# eeZeePower.net
KiCad netlist of a schematic drawn in EAGLE
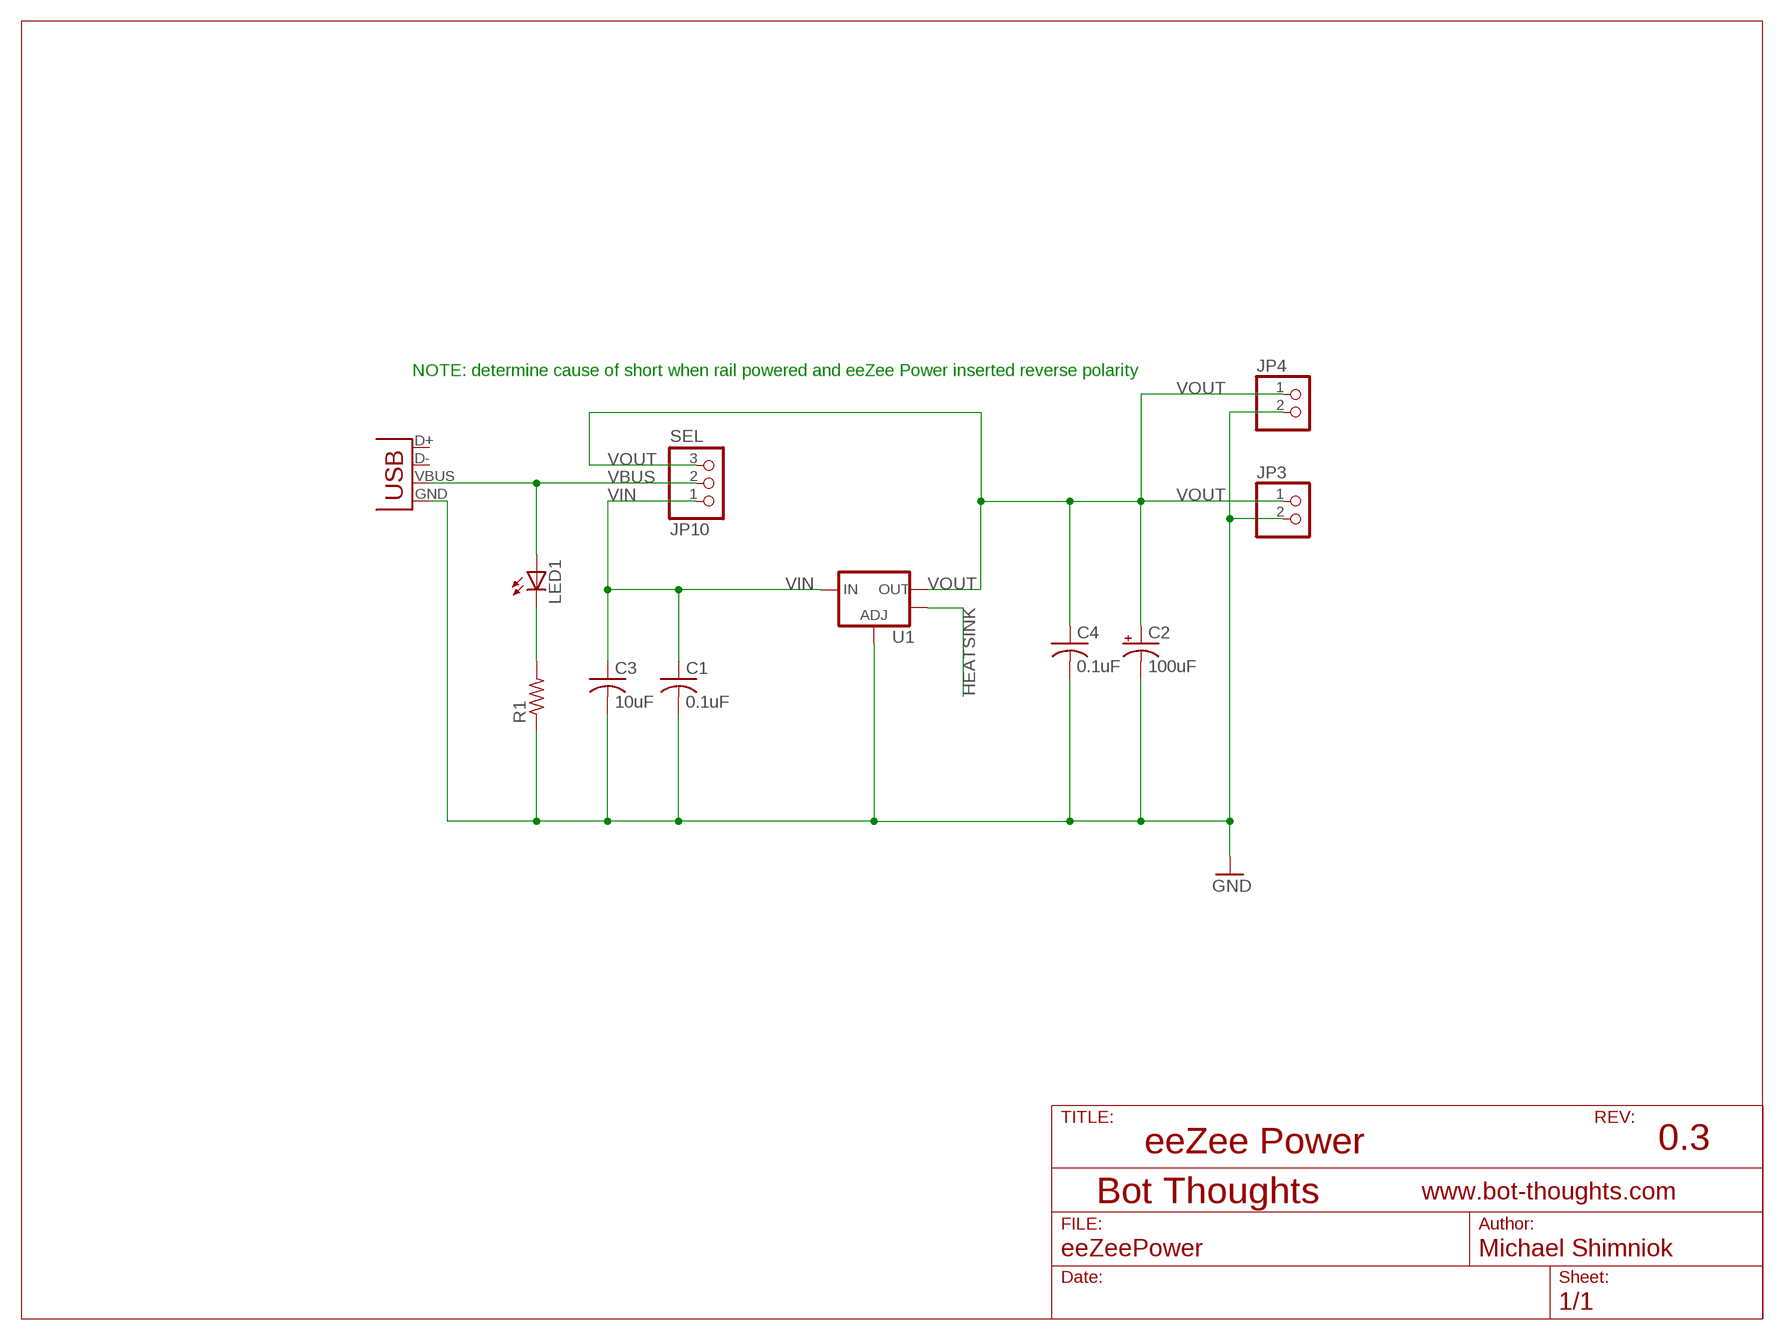
[diagram p0: schematic, sheet 1]

(export (version "E")
  (design (tool "Eeschema 10.0.6"))
  (components
    (comp (ref "C1")
      (value "0.1uF")
      (footprint "eagle-import:C0603")
      (libsource (lib "eagle-import") (part "C-USC0603"))
    )
    (comp (ref "C2")
      (value "100uF")
      (footprint "eagle-import:SMC_B")
      (libsource (lib "eagle-import") (part "CPOL-USSMCB"))
    )
    (comp (ref "C3")
      (value "10uF")
      (footprint "eagle-import:C0603")
      (libsource (lib "eagle-import") (part "C-USC0603"))
    )
    (comp (ref "C4")
      (value "0.1uF")
      (footprint "eagle-import:C0603")
      (libsource (lib "eagle-import") (part "C-USC0603"))
    )
    (comp (ref "JP1")
      (value "USBSMD")
      (footprint "eagle-import:USB-MINIB")
      (libsource (lib "eagle-import") (part "USBSMD"))
    )
    (comp (ref "JP3")
      (value "PINHD-1X02_2.54-S")
      (footprint "eagle-import:1X02-S")
      (libsource (lib "eagle-import") (part "PINHD-1X02_2.54-S"))
    )
    (comp (ref "JP4")
      (value "PINHD-1X02_2.54-S")
      (footprint "eagle-import:1X02-S")
      (libsource (lib "eagle-import") (part "PINHD-1X02_2.54-S"))
    )
    (comp (ref "JP10")
      (value "SEL")
      (footprint "eagle-import:1X03-S")
      (libsource (lib "eagle-import") (part "PINHD-1X03_2.54-S"))
    )
    (comp (ref "LED1")
      (value "LEDCHIPLED_1206")
      (footprint "eagle-import:CHIPLED_1206")
      (libsource (lib "eagle-import") (part "LEDCHIPLED_1206"))
    )
    (comp (ref "R1")
      (value "R-US_R0603")
      (footprint "eagle-import:R0603")
      (libsource (lib "eagle-import") (part "R-US_R0603"))
    )
    (comp (ref "U1")
      (value "V_REG_LM1117SOT223")
      (footprint "eagle-import:SOT223")
      (libsource (lib "eagle-import") (part "V_REG_LM1117SOT223"))
    )
  )
  (nets
    (net (code "1") (name "/HEATSINK") (class "Default")
      (node (ref "U1") (pin "4") (pinfunction "OUT_4") (pintype "output"))
    )
    (net (code "2") (name "/VBUS") (class "Default")
      (node (ref "JP1") (pin "VBUS") (pinfunction "VBUS_VBUS") (pintype "bidirectional"))
      (node (ref "JP10") (pin "2") (pinfunction "2_2") (pintype "passive"))
      (node (ref "LED1") (pin "A") (pinfunction "A_A") (pintype "passive"))
    )
    (net (code "3") (name "/VIN") (class "Default")
      (node (ref "C1") (pin "1") (pinfunction "1_1") (pintype "passive"))
      (node (ref "C3") (pin "1") (pinfunction "1_1") (pintype "passive"))
      (node (ref "JP10") (pin "1") (pinfunction "1_1") (pintype "passive"))
      (node (ref "U1") (pin "3") (pinfunction "IN_3") (pintype "input"))
    )
    (net (code "4") (name "/VOUT") (class "Default")
      (node (ref "C2") (pin "+") (pinfunction "+_+") (pintype "passive"))
      (node (ref "C4") (pin "1") (pinfunction "1_1") (pintype "passive"))
      (node (ref "JP10") (pin "3") (pinfunction "3_3") (pintype "passive"))
      (node (ref "JP3") (pin "1") (pinfunction "1_1") (pintype "passive"))
      (node (ref "JP4") (pin "1") (pinfunction "1_1") (pintype "passive"))
      (node (ref "U1") (pin "2") (pinfunction "OUT_2") (pintype "output"))
    )
    (net (code "5") (name "GND") (class "Default")
      (node (ref "C1") (pin "2") (pinfunction "2_2") (pintype "passive"))
      (node (ref "C2") (pin "-") (pinfunction "-_-") (pintype "passive"))
      (node (ref "C3") (pin "2") (pinfunction "2_2") (pintype "passive"))
      (node (ref "C4") (pin "2") (pinfunction "2_2") (pintype "passive"))
      (node (ref "JP1") (pin "GND") (pinfunction "GND_GND") (pintype "bidirectional"))
      (node (ref "JP3") (pin "2") (pinfunction "2_2") (pintype "passive"))
      (node (ref "JP4") (pin "2") (pinfunction "2_2") (pintype "passive"))
      (node (ref "R1") (pin "1") (pinfunction "1_1") (pintype "passive"))
      (node (ref "U1") (pin "1") (pinfunction "ADJ_1") (pintype "input"))
    )
    (net (code "6") (name "Net-(LED1-PadC)") (class "Default")
      (node (ref "LED1") (pin "C") (pinfunction "C_C") (pintype "passive"))
      (node (ref "R1") (pin "2") (pinfunction "2_2") (pintype "passive"))
    )
    (net (code "7") (name "unconnected-(JP1-PadD+)") (class "Default")
      (node (ref "JP1") (pin "D+") (pinfunction "D+_D+") (pintype "bidirectional"))
    )
    (net (code "8") (name "unconnected-(JP1-PadD-)") (class "Default")
      (node (ref "JP1") (pin "D-") (pinfunction "D-_D-") (pintype "bidirectional"))
    )
  )
)
